# FREEPIXEL.net
KiCad netlist of a schematic drawn in EAGLE
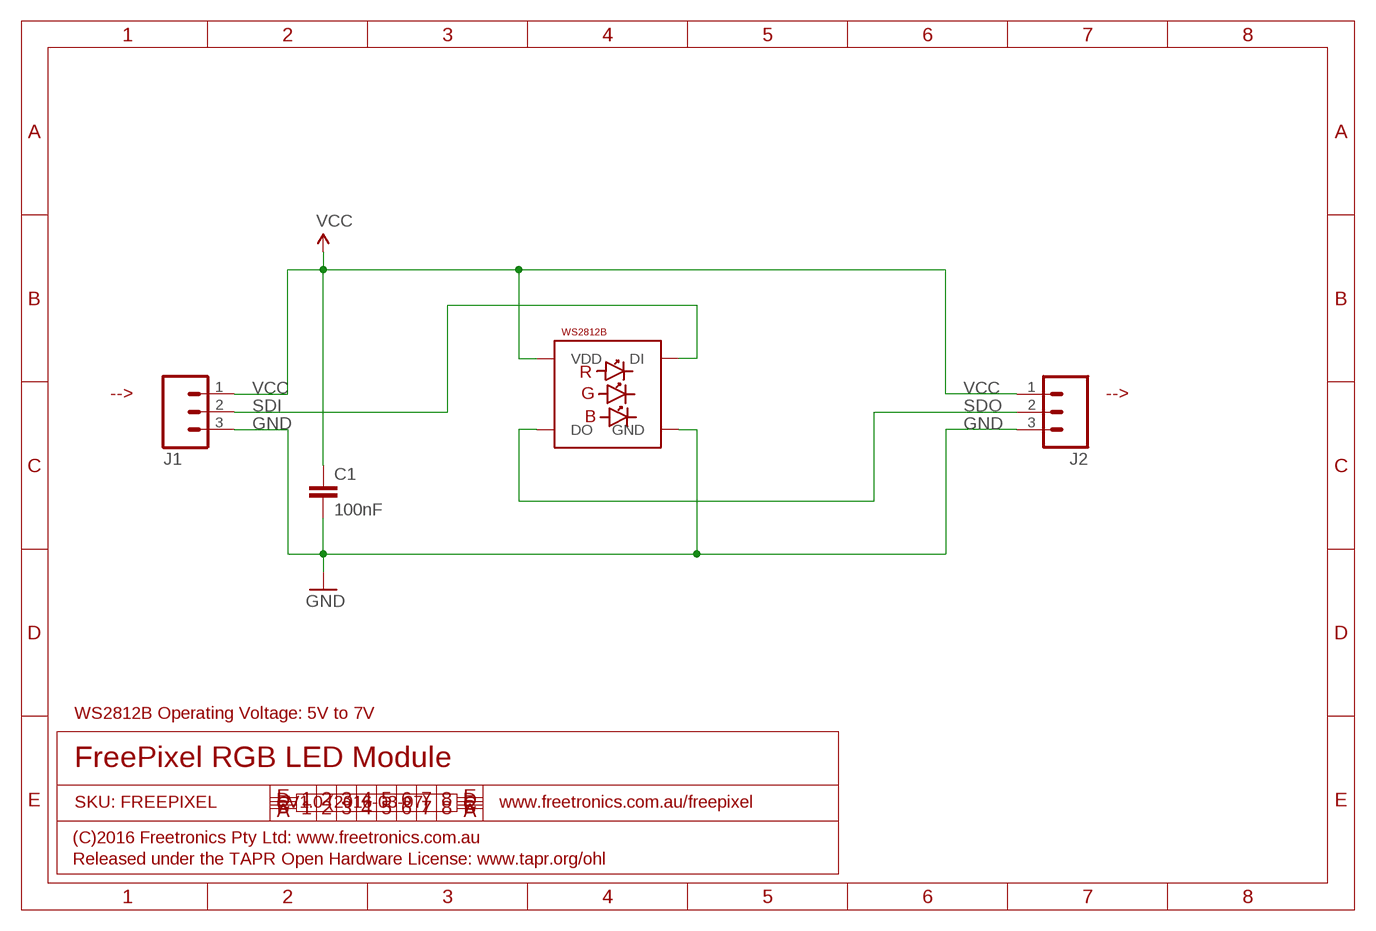
[diagram p0: schematic, sheet 1]

(export (version "E")
  (design (tool "Eeschema 10.0.6"))
  (components
    (comp (ref "C1")
      (value "100nF")
      (footprint "eagle-import:0603")
      (libsource (lib "eagle-import") (part "CAP0603"))
    )
    (comp (ref "J1")
      (value "M03PTH")
      (footprint "eagle-import:1X03")
      (libsource (lib "eagle-import") (part "M03PTH"))
    )
    (comp (ref "J2")
      (value "M03PTH")
      (footprint "eagle-import:1X03")
      (libsource (lib "eagle-import") (part "M03PTH"))
    )
    (comp (ref "LED1")
      (value "WS2812B5050")
      (footprint "eagle-import:WS2812B")
      (libsource (lib "eagle-import") (part "WS2812B5050"))
    )
  )
  (nets
    (net (code "1") (name "/SDI") (class "Default")
      (node (ref "J1") (pin "2") (pinfunction "2_2") (pintype "passive"))
      (node (ref "LED1") (pin "4-DIN") (pinfunction "DI_4-DIN") (pintype "input"))
    )
    (net (code "2") (name "/SDO") (class "Default")
      (node (ref "J2") (pin "2") (pinfunction "2_2") (pintype "passive"))
      (node (ref "LED1") (pin "2-DOUT") (pinfunction "DO_2-DOUT") (pintype "output"))
    )
    (net (code "3") (name "GND") (class "Default")
      (node (ref "C1") (pin "2") (pinfunction "2_2") (pintype "passive"))
      (node (ref "J1") (pin "3") (pinfunction "3_3") (pintype "passive"))
      (node (ref "J2") (pin "3") (pinfunction "3_3") (pintype "passive"))
      (node (ref "LED1") (pin "3-GND") (pinfunction "GND_3-GND") (pintype "power_in"))
    )
    (net (code "4") (name "VCC") (class "Default")
      (node (ref "C1") (pin "1") (pinfunction "1_1") (pintype "passive"))
      (node (ref "J1") (pin "1") (pinfunction "1_1") (pintype "passive"))
      (node (ref "J2") (pin "1") (pinfunction "1_1") (pintype "passive"))
      (node (ref "LED1") (pin "1-VDD") (pinfunction "VDD_1-VDD") (pintype "power_in"))
    )
  )
)
